# main.net
KiCad netlist of a schematic drawn in Altium Designer
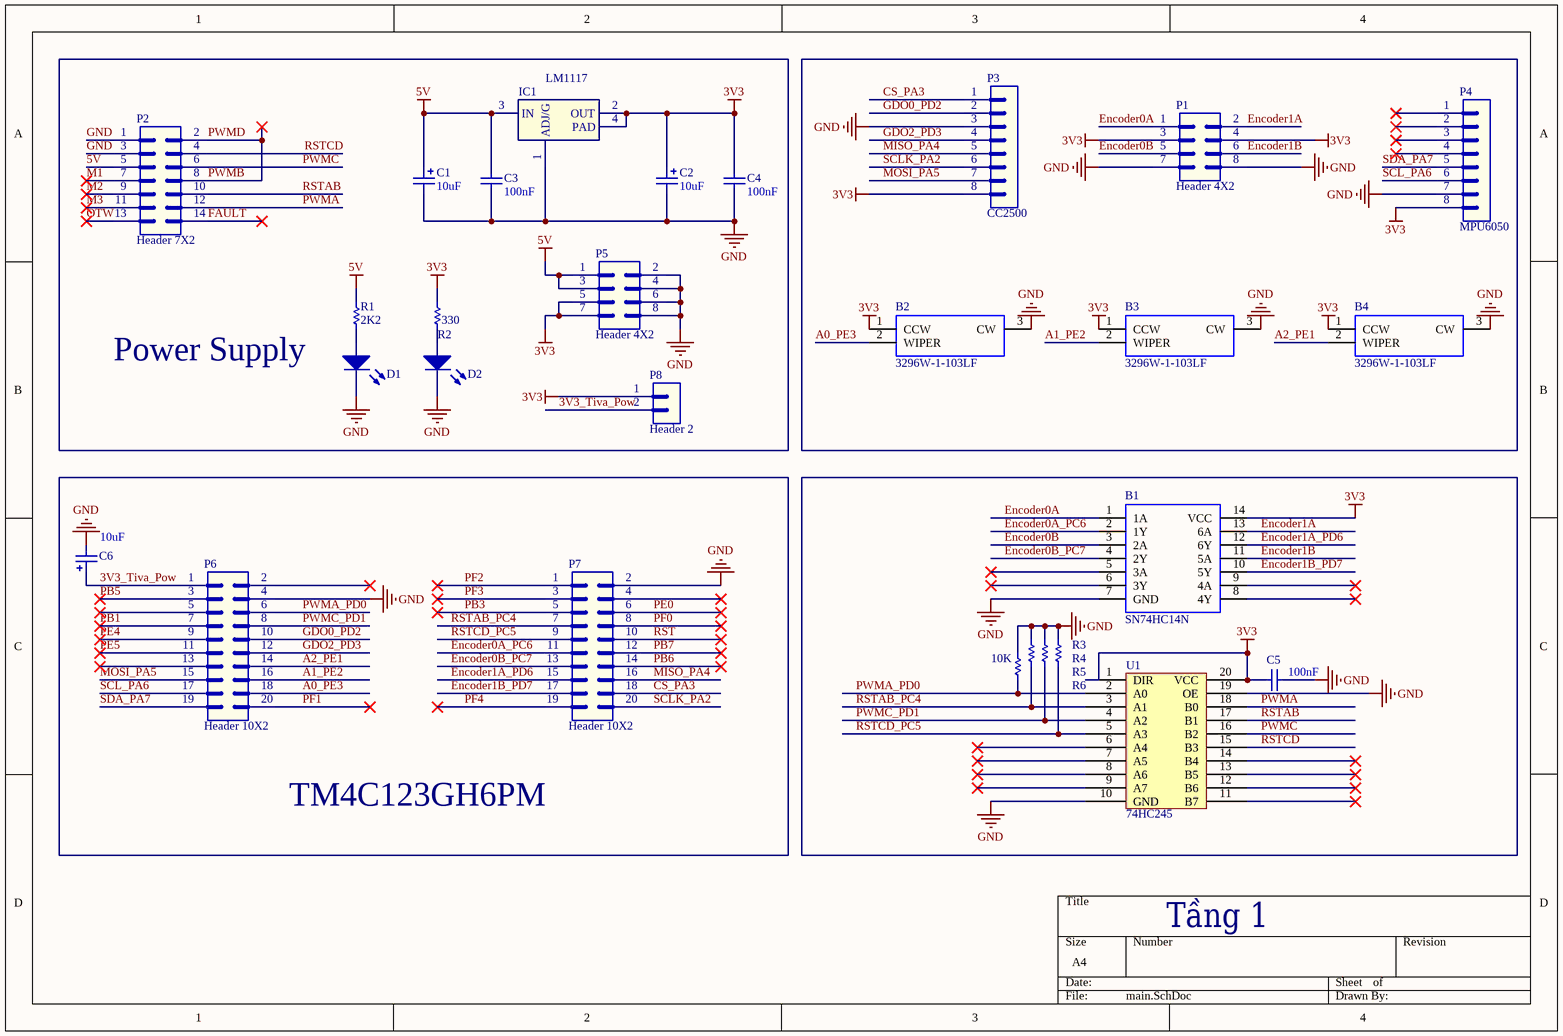
[diagram p0: main.SchDoc]

(export (version "E")
  (design (tool "Eeschema 10.0.6"))
  (components
    (comp (ref "B1")
      (value "SN74HC14N")
      (footprint "DIP254P762X508-14")
      (description "Hex invertor,SN74HC14N DIP14 2-6V 25pcs")
      (fields (field (name "RS PART NUMBER") "0442943"))
      (libsource (lib "SN74HC14N") (part "SN74HC14N"))
    )
    (comp (ref "B2")
      (value "3296W-1-103LF")
      (footprint "SHDR3W54P0X254_1X3_953X483X1155P")
      (fields (field (name "RS PART NUMBER") "5219647P"))
      (libsource (lib "3296W-1-103LF") (part "3296W-1-103LF"))
    )
    (comp (ref "B3")
      (value "3296W-1-103LF")
      (footprint "SHDR3W54P0X254_1X3_953X483X1155P")
      (fields (field (name "RS PART NUMBER") "5219647P"))
      (libsource (lib "3296W-1-103LF") (part "3296W-1-103LF"))
    )
    (comp (ref "B4")
      (value "3296W-1-103LF")
      (footprint "SHDR3W54P0X254_1X3_953X483X1155P")
      (fields (field (name "RS PART NUMBER") "5219647P"))
      (libsource (lib "3296W-1-103LF") (part "3296W-1-103LF"))
    )
    (comp (ref "C1")
      (value "Capacitors")
      (footprint "CAP TANTALUM SMD-1206")
      (description "Capacitors Tantalum")
      (fields
        (field (name "MANUFACTURER") "Kemet")
        (field (name "MANUFACTURER PART NUMBER") "T491A106K010AT")
        (field (name "CAPACITANCE") "10uF")
      )
      (libsource (lib "PIF_C16_lib") (part "Cap Pol Tantalum"))
    )
    (comp (ref "C2")
      (value "Capacitors")
      (footprint "CAP TANTALUM SMD-1206")
      (description "Capacitors Tantalum")
      (fields
        (field (name "MANUFACTURER") "Kemet")
        (field (name "MANUFACTURER PART NUMBER") "T491A106K010AT")
        (field (name "CAPACITANCE") "10uF")
      )
      (libsource (lib "PIF_C16_lib") (part "Cap Pol Tantalum"))
    )
    (comp (ref "C3")
      (value "100nF")
      (footprint "CAP-SM-0805")
      (description "Capacitor")
      (fields (field (name "Comment") "Cap Non-Pol SMD"))
      (libsource (lib "PIF_C16_lib") (part "Cap Non-Pol SMD"))
    )
    (comp (ref "C4")
      (value "100nF")
      (footprint "CAP-SM-0805")
      (description "Capacitor")
      (fields (field (name "Comment") "Cap Non-Pol SMD"))
      (libsource (lib "PIF_C16_lib") (part "Cap Non-Pol SMD"))
    )
    (comp (ref "C5")
      (value "100nF")
      (footprint "CN1")
      (description "Capacitor")
      (fields (field (name "Comment") "Cap Non-Pol"))
      (libsource (lib "PIF_C16_lib") (part "Cap Non-Pol"))
    )
    (comp (ref "C6")
      (value "Capacitors")
      (footprint "CAP TANTALUM SMD-1206")
      (description "Capacitors Tantalum")
      (fields
        (field (name "MANUFACTURER") "Kemet")
        (field (name "MANUFACTURER PART NUMBER") "T491A106K010AT")
        (field (name "CAPACITANCE") "10uF")
      )
      (libsource (lib "PIF_C16_lib") (part "Cap Pol Tantalum"))
    )
    (comp (ref "D1") (value "LED") (footprint "LED-5mm") (libsource (lib "PIF_C16_lib") (part "LED")))
    (comp (ref "D2") (value "LED") (footprint "LED-5mm") (libsource (lib "PIF_C16_lib") (part "LED")))
    (comp (ref "IC1")
      (value "LM1117")
      (footprint "SOT223-4N")
      (description "Available in 1.8V, 2.5V, 2.85V, 3.3V, 5V, and  Adjustable Versions")
      (libsource (lib "PIF_C16_lib") (part "LM1117"))
    )
    (comp (ref "P1")
      (value "Header 4X2")
      (footprint "JP4x2")
      (description "Header, 4-Pin, Dual row")
      (fields (field (name "PUBLISHER") "Altium Limited"))
      (libsource (lib "PIF_C16_lib") (part "Header 4X2"))
    )
    (comp (ref "P2")
      (value "Header 7X2")
      (footprint "JP7X2")
      (description "Header, 7-Pin, Dual row")
      (fields (field (name "PUBLISHER") "Altium Limited"))
      (libsource (lib "PIF_C16_lib") (part "Header 7X2"))
    )
    (comp (ref "P3")
      (value "CC2500")
      (footprint "JP8")
      (description "Header, 8-Pin")
      (fields (field (name "PUBLISHER") "Altium Limited"))
      (libsource (lib "PIF_C16_lib") (part "Header 8"))
    )
    (comp (ref "P4")
      (value "MPU6050")
      (footprint "JP8")
      (description "Header, 8-Pin")
      (fields (field (name "PUBLISHER") "Altium Limited"))
      (libsource (lib "PIF_C16_lib") (part "Header 8"))
    )
    (comp (ref "P5")
      (value "Header 4X2")
      (footprint "JP4x2")
      (description "Header, 4-Pin, Dual row")
      (fields (field (name "PUBLISHER") "Altium Limited"))
      (libsource (lib "PIF_C16_lib") (part "Header 4X2"))
    )
    (comp (ref "P6")
      (value "Header 10X2")
      (footprint "JP10X2")
      (description "Header, 10-Pin, Dual row")
      (fields (field (name "PUBLISHER") "Altium Limited"))
      (libsource (lib "PIF_C16_lib") (part "Header 10X2"))
    )
    (comp (ref "P7")
      (value "Header 10X2")
      (footprint "JP10X2")
      (description "Header, 10-Pin, Dual row")
      (fields (field (name "PUBLISHER") "Altium Limited"))
      (libsource (lib "PIF_C16_lib") (part "Header 10X2"))
    )
    (comp (ref "P8")
      (value "Header 2")
      (footprint "JP2")
      (description "Header, 2-Pin")
      (fields (field (name "PUBLISHER") "Altium Limited"))
      (libsource (lib "PIF_C16_lib") (part "Header 2"))
    )
    (comp (ref "R1")
      (value "2K2")
      (footprint "RES 1/2W")
      (fields (field (name "Comment") "Resistor 1/4W"))
      (libsource (lib "PIF_C16_lib") (part "RES"))
    )
    (comp (ref "R2")
      (value "330")
      (footprint "RES 1/2W")
      (fields (field (name "Comment") "Resistor 1/4W"))
      (libsource (lib "PIF_C16_lib") (part "RES"))
    )
    (comp (ref "R3")
      (value "Resistor 1/4W")
      (footprint "RES 1/2W")
      (libsource (lib "PIF_C16_lib") (part "RES"))
    )
    (comp (ref "R4")
      (value "Resistor 1/4W")
      (footprint "RES 1/2W")
      (libsource (lib "PIF_C16_lib") (part "RES"))
    )
    (comp (ref "R5")
      (value "Resistor 1/4W")
      (footprint "RES 1/2W")
      (libsource (lib "PIF_C16_lib") (part "RES"))
    )
    (comp (ref "R6")
      (value "10K")
      (footprint "RES 1/2W")
      (fields (field (name "Comment") "Resistor 1/4W"))
      (libsource (lib "PIF_C16_lib") (part "RES"))
    )
    (comp (ref "U1")
      (value "74HC245")
      (footprint "DIP20/W0.3")
      (description "Octal bus tranceiver")
      (libsource (lib "syhaunguyen") (part "74HC245"))
    )
  )
  (nets
    (net (code "1") (name "/3V3_Tiva_Pow") (class "Default")
      (node (ref "C6") (pin "1") (pinfunction "1_1") (pintype "passive"))
      (node (ref "P6") (pin "1") (pinfunction "1_1") (pintype "passive"))
      (node (ref "P8") (pin "2") (pinfunction "2_2") (pintype "passive"))
    )
    (net (code "2") (name "/A0_PE3") (class "Default")
      (node (ref "B2") (pin "2") (pinfunction "WIPER_2") (pintype "passive"))
      (node (ref "P6") (pin "18") (pinfunction "18_18") (pintype "passive"))
    )
    (net (code "3") (name "/A1_PE2") (class "Default")
      (node (ref "B3") (pin "2") (pinfunction "WIPER_2") (pintype "passive"))
      (node (ref "P6") (pin "16") (pinfunction "16_16") (pintype "passive"))
    )
    (net (code "4") (name "/A2_PE1") (class "Default")
      (node (ref "B4") (pin "2") (pinfunction "WIPER_2") (pintype "passive"))
      (node (ref "P6") (pin "14") (pinfunction "14_14") (pintype "passive"))
    )
    (net (code "5") (name "/CS_PA3") (class "Default")
      (node (ref "P3") (pin "1") (pinfunction "1_1") (pintype "passive"))
      (node (ref "P7") (pin "18") (pinfunction "18_18") (pintype "passive"))
    )
    (net (code "6") (name "/Encoder0A") (class "Default")
      (node (ref "B1") (pin "1") (pinfunction "1A_1") (pintype "passive"))
      (node (ref "P1") (pin "1") (pinfunction "1_1") (pintype "passive"))
    )
    (net (code "7") (name "/Encoder0A_PC6") (class "Default")
      (node (ref "B1") (pin "2") (pinfunction "1Y_2") (pintype "passive"))
      (node (ref "P7") (pin "11") (pinfunction "11_11") (pintype "passive"))
    )
    (net (code "8") (name "/Encoder0B") (class "Default")
      (node (ref "B1") (pin "3") (pinfunction "2A_3") (pintype "passive"))
      (node (ref "P1") (pin "5") (pinfunction "5_5") (pintype "passive"))
    )
    (net (code "9") (name "/Encoder0B_PC7") (class "Default")
      (node (ref "B1") (pin "4") (pinfunction "2Y_4") (pintype "passive"))
      (node (ref "P7") (pin "13") (pinfunction "13_13") (pintype "passive"))
    )
    (net (code "10") (name "/Encoder1A") (class "Default")
      (node (ref "B1") (pin "13") (pinfunction "6A_13") (pintype "passive"))
      (node (ref "P1") (pin "2") (pinfunction "2_2") (pintype "passive"))
    )
    (net (code "11") (name "/Encoder1A_PD6") (class "Default")
      (node (ref "B1") (pin "12") (pinfunction "6Y_12") (pintype "passive"))
      (node (ref "P7") (pin "15") (pinfunction "15_15") (pintype "passive"))
    )
    (net (code "12") (name "/Encoder1B") (class "Default")
      (node (ref "B1") (pin "11") (pinfunction "5A_11") (pintype "passive"))
      (node (ref "P1") (pin "6") (pinfunction "6_6") (pintype "passive"))
    )
    (net (code "13") (name "/Encoder1B_PD7") (class "Default")
      (node (ref "B1") (pin "10") (pinfunction "5Y_10") (pintype "passive"))
      (node (ref "P7") (pin "17") (pinfunction "17_17") (pintype "passive"))
    )
    (net (code "14") (name "/FAULT") (class "Default")
      (node (ref "P2") (pin "14") (pinfunction "14_14") (pintype "passive+no_connect"))
    )
    (net (code "15") (name "/GDO0_PD2") (class "Default")
      (node (ref "P3") (pin "2") (pinfunction "2_2") (pintype "passive"))
      (node (ref "P6") (pin "10") (pinfunction "10_10") (pintype "passive"))
    )
    (net (code "16") (name "/GDO2_PD3") (class "Default")
      (node (ref "P3") (pin "4") (pinfunction "4_4") (pintype "passive"))
      (node (ref "P6") (pin "12") (pinfunction "12_12") (pintype "passive"))
    )
    (net (code "17") (name "/M1") (class "Default")
      (node (ref "P2") (pin "7") (pinfunction "7_7") (pintype "passive+no_connect"))
    )
    (net (code "18") (name "/M2") (class "Default")
      (node (ref "P2") (pin "9") (pinfunction "9_9") (pintype "passive+no_connect"))
    )
    (net (code "19") (name "/M3") (class "Default")
      (node (ref "P2") (pin "11") (pinfunction "11_11") (pintype "passive+no_connect"))
    )
    (net (code "20") (name "/MISO_PA4") (class "Default")
      (node (ref "P3") (pin "5") (pinfunction "5_5") (pintype "passive"))
      (node (ref "P7") (pin "16") (pinfunction "16_16") (pintype "passive"))
    )
    (net (code "21") (name "/MOSI_PA5") (class "Default")
      (node (ref "P3") (pin "7") (pinfunction "7_7") (pintype "passive"))
      (node (ref "P6") (pin "15") (pinfunction "15_15") (pintype "passive"))
    )
    (net (code "22") (name "/OTW") (class "Default")
      (node (ref "P2") (pin "13") (pinfunction "13_13") (pintype "passive+no_connect"))
    )
    (net (code "23") (name "/PB1") (class "Default")
      (node (ref "P6") (pin "7") (pinfunction "7_7") (pintype "passive+no_connect"))
    )
    (net (code "24") (name "/PB3") (class "Default")
      (node (ref "P7") (pin "5") (pinfunction "5_5") (pintype "passive+no_connect"))
    )
    (net (code "25") (name "/PB5") (class "Default")
      (node (ref "P6") (pin "3") (pinfunction "3_3") (pintype "passive+no_connect"))
    )
    (net (code "26") (name "/PB6") (class "Default")
      (node (ref "P7") (pin "14") (pinfunction "14_14") (pintype "passive+no_connect"))
    )
    (net (code "27") (name "/PB7") (class "Default")
      (node (ref "P7") (pin "12") (pinfunction "12_12") (pintype "passive+no_connect"))
    )
    (net (code "28") (name "/PE0") (class "Default")
      (node (ref "P7") (pin "6") (pinfunction "6_6") (pintype "passive+no_connect"))
    )
    (net (code "29") (name "/PE4") (class "Default")
      (node (ref "P6") (pin "9") (pinfunction "9_9") (pintype "passive+no_connect"))
    )
    (net (code "30") (name "/PE5") (class "Default")
      (node (ref "P6") (pin "11") (pinfunction "11_11") (pintype "passive+no_connect"))
    )
    (net (code "31") (name "/PF0") (class "Default")
      (node (ref "P7") (pin "8") (pinfunction "8_8") (pintype "passive+no_connect"))
    )
    (net (code "32") (name "/PF1") (class "Default")
      (node (ref "P6") (pin "20") (pinfunction "20_20") (pintype "passive+no_connect"))
    )
    (net (code "33") (name "/PF2") (class "Default")
      (node (ref "P7") (pin "1") (pinfunction "1_1") (pintype "passive+no_connect"))
    )
    (net (code "34") (name "/PF3") (class "Default")
      (node (ref "P7") (pin "3") (pinfunction "3_3") (pintype "passive+no_connect"))
    )
    (net (code "35") (name "/PF4") (class "Default")
      (node (ref "P7") (pin "19") (pinfunction "19_19") (pintype "passive+no_connect"))
    )
    (net (code "36") (name "/PWMA") (class "Default")
      (node (ref "P2") (pin "12") (pinfunction "12_12") (pintype "passive"))
      (node (ref "U1") (pin "18") (pinfunction "B0_18") (pintype "passive"))
    )
    (net (code "37") (name "/PWMA_PD0") (class "Default")
      (node (ref "P6") (pin "6") (pinfunction "6_6") (pintype "passive"))
      (node (ref "R6") (pin "1") (pintype "passive"))
      (node (ref "U1") (pin "2") (pinfunction "A0_2") (pintype "passive"))
    )
    (net (code "38") (name "/PWMB") (class "Default")
      (node (ref "P2") (pin "2") (pinfunction "2_2") (pintype "passive"))
      (node (ref "P2") (pin "8") (pinfunction "8_8") (pintype "passive"))
    )
    (net (code "39") (name "/PWMC") (class "Default")
      (node (ref "P2") (pin "6") (pinfunction "6_6") (pintype "passive"))
      (node (ref "U1") (pin "16") (pinfunction "B2_16") (pintype "passive"))
    )
    (net (code "40") (name "/PWMC_PD1") (class "Default")
      (node (ref "P6") (pin "8") (pinfunction "8_8") (pintype "passive"))
      (node (ref "R4") (pin "1") (pintype "passive"))
      (node (ref "U1") (pin "4") (pinfunction "A2_4") (pintype "passive"))
    )
    (net (code "41") (name "/RST") (class "Default")
      (node (ref "P7") (pin "10") (pinfunction "10_10") (pintype "passive+no_connect"))
    )
    (net (code "42") (name "/RSTAB") (class "Default")
      (node (ref "P2") (pin "10") (pinfunction "10_10") (pintype "passive"))
      (node (ref "U1") (pin "17") (pinfunction "B1_17") (pintype "passive"))
    )
    (net (code "43") (name "/RSTAB_PC4") (class "Default")
      (node (ref "P7") (pin "7") (pinfunction "7_7") (pintype "passive"))
      (node (ref "R3") (pin "1") (pintype "passive"))
      (node (ref "U1") (pin "3") (pinfunction "A1_3") (pintype "passive"))
    )
    (net (code "44") (name "/RSTCD") (class "Default")
      (node (ref "P2") (pin "4") (pinfunction "4_4") (pintype "passive"))
      (node (ref "U1") (pin "15") (pinfunction "B3_15") (pintype "passive"))
    )
    (net (code "45") (name "/RSTCD_PC5") (class "Default")
      (node (ref "P7") (pin "9") (pinfunction "9_9") (pintype "passive"))
      (node (ref "R5") (pin "1") (pintype "passive"))
      (node (ref "U1") (pin "5") (pinfunction "A3_5") (pintype "passive"))
    )
    (net (code "46") (name "/SCLK_PA2") (class "Default")
      (node (ref "P3") (pin "6") (pinfunction "6_6") (pintype "passive"))
      (node (ref "P7") (pin "20") (pinfunction "20_20") (pintype "passive"))
    )
    (net (code "47") (name "/SCL_PA6") (class "Default")
      (node (ref "P4") (pin "6") (pinfunction "6_6") (pintype "passive"))
      (node (ref "P6") (pin "17") (pinfunction "17_17") (pintype "passive"))
    )
    (net (code "48") (name "/SDA_PA7") (class "Default")
      (node (ref "P4") (pin "5") (pinfunction "5_5") (pintype "passive"))
      (node (ref "P6") (pin "19") (pinfunction "19_19") (pintype "passive"))
    )
    (net (code "49") (name "3V3") (class "Default")
      (node (ref "B1") (pin "14") (pinfunction "VCC_14") (pintype "passive"))
      (node (ref "B2") (pin "1") (pinfunction "CCW_1") (pintype "passive"))
      (node (ref "B3") (pin "1") (pinfunction "CCW_1") (pintype "passive"))
      (node (ref "B4") (pin "1") (pinfunction "CCW_1") (pintype "passive"))
      (node (ref "C2") (pin "1") (pinfunction "1_1") (pintype "passive"))
      (node (ref "C4") (pin "2") (pinfunction "2_2") (pintype "passive"))
      (node (ref "C5") (pin "1") (pinfunction "1_1") (pintype "passive"))
      (node (ref "IC1") (pin "2") (pinfunction "OUT_2") (pintype "passive"))
      (node (ref "IC1") (pin "4") (pinfunction "PAD_4") (pintype "passive"))
      (node (ref "P1") (pin "3") (pinfunction "3_3") (pintype "passive"))
      (node (ref "P1") (pin "4") (pinfunction "4_4") (pintype "passive"))
      (node (ref "P3") (pin "8") (pinfunction "8_8") (pintype "passive"))
      (node (ref "P4") (pin "8") (pinfunction "8_8") (pintype "passive"))
      (node (ref "P5") (pin "5") (pinfunction "5_5") (pintype "passive"))
      (node (ref "P5") (pin "7") (pinfunction "7_7") (pintype "passive"))
      (node (ref "P8") (pin "1") (pinfunction "1_1") (pintype "passive"))
      (node (ref "R2") (pin "2") (pintype "passive"))
      (node (ref "U1") (pin "1") (pinfunction "DIR_1") (pintype "passive"))
      (node (ref "U1") (pin "20") (pinfunction "VCC_20") (pintype "power_in"))
    )
    (net (code "50") (name "5V") (class "Default")
      (node (ref "C1") (pin "1") (pinfunction "1_1") (pintype "passive"))
      (node (ref "C3") (pin "2") (pinfunction "2_2") (pintype "passive"))
      (node (ref "IC1") (pin "3") (pinfunction "IN_3") (pintype "passive"))
      (node (ref "P2") (pin "5") (pinfunction "5_5") (pintype "passive"))
      (node (ref "P5") (pin "1") (pinfunction "1_1") (pintype "passive"))
      (node (ref "P5") (pin "3") (pinfunction "3_3") (pintype "passive"))
      (node (ref "R1") (pin "2") (pintype "passive"))
    )
    (net (code "51") (name "GND") (class "Default")
      (node (ref "B1") (pin "7") (pinfunction "GND_7") (pintype "passive"))
      (node (ref "B2") (pin "3") (pinfunction "CW_3") (pintype "passive"))
      (node (ref "B3") (pin "3") (pinfunction "CW_3") (pintype "passive"))
      (node (ref "B4") (pin "3") (pinfunction "CW_3") (pintype "passive"))
      (node (ref "C1") (pin "2") (pinfunction "2_2") (pintype "passive"))
      (node (ref "C2") (pin "2") (pinfunction "2_2") (pintype "passive"))
      (node (ref "C3") (pin "1") (pinfunction "1_1") (pintype "passive"))
      (node (ref "C4") (pin "1") (pinfunction "1_1") (pintype "passive"))
      (node (ref "C5") (pin "2") (pinfunction "2_2") (pintype "passive"))
      (node (ref "C6") (pin "2") (pinfunction "2_2") (pintype "passive"))
      (node (ref "D1") (pin "2") (pinfunction "K_2") (pintype "passive"))
      (node (ref "D2") (pin "2") (pinfunction "K_2") (pintype "passive"))
      (node (ref "IC1") (pin "1") (pinfunction "ADJ/G_1") (pintype "passive"))
      (node (ref "P1") (pin "7") (pinfunction "7_7") (pintype "passive"))
      (node (ref "P1") (pin "8") (pinfunction "8_8") (pintype "passive"))
      (node (ref "P2") (pin "1") (pinfunction "1_1") (pintype "passive"))
      (node (ref "P2") (pin "3") (pinfunction "3_3") (pintype "passive"))
      (node (ref "P3") (pin "3") (pinfunction "3_3") (pintype "passive"))
      (node (ref "P4") (pin "7") (pinfunction "7_7") (pintype "passive"))
      (node (ref "P5") (pin "2") (pinfunction "2_2") (pintype "passive"))
      (node (ref "P5") (pin "4") (pinfunction "4_4") (pintype "passive"))
      (node (ref "P5") (pin "6") (pinfunction "6_6") (pintype "passive"))
      (node (ref "P5") (pin "8") (pinfunction "8_8") (pintype "passive"))
      (node (ref "P6") (pin "4") (pinfunction "4_4") (pintype "passive"))
      (node (ref "P7") (pin "2") (pinfunction "2_2") (pintype "passive"))
      (node (ref "R3") (pin "2") (pintype "passive"))
      (node (ref "R4") (pin "2") (pintype "passive"))
      (node (ref "R5") (pin "2") (pintype "passive"))
      (node (ref "R6") (pin "2") (pintype "passive"))
      (node (ref "U1") (pin "10") (pinfunction "GND_10") (pintype "power_in"))
      (node (ref "U1") (pin "19") (pinfunction "OE_19") (pintype "passive"))
    )
    (net (code "52") (name "Net-(D1-A)") (class "Default")
      (node (ref "D1") (pin "1") (pinfunction "A_1") (pintype "passive"))
      (node (ref "R1") (pin "1") (pintype "passive"))
    )
    (net (code "53") (name "Net-(D2-A)") (class "Default")
      (node (ref "D2") (pin "1") (pinfunction "A_1") (pintype "passive"))
      (node (ref "R2") (pin "1") (pintype "passive"))
    )
    (net (code "54") (name "unconnected-(B1-3A-Pad5)") (class "Default")
      (node (ref "B1") (pin "5") (pinfunction "3A_5") (pintype "passive+no_connect"))
    )
    (net (code "55") (name "unconnected-(B1-3Y-Pad6)") (class "Default")
      (node (ref "B1") (pin "6") (pinfunction "3Y_6") (pintype "passive+no_connect"))
    )
    (net (code "56") (name "unconnected-(B1-4A-Pad9)") (class "Default")
      (node (ref "B1") (pin "9") (pinfunction "4A_9") (pintype "passive+no_connect"))
    )
    (net (code "57") (name "unconnected-(B1-4Y-Pad8)") (class "Default")
      (node (ref "B1") (pin "8") (pinfunction "4Y_8") (pintype "passive+no_connect"))
    )
    (net (code "58") (name "unconnected-(P4-Pad1)") (class "Default")
      (node (ref "P4") (pin "1") (pinfunction "1_1") (pintype "passive+no_connect"))
    )
    (net (code "59") (name "unconnected-(P4-Pad2)") (class "Default")
      (node (ref "P4") (pin "2") (pinfunction "2_2") (pintype "passive+no_connect"))
    )
    (net (code "60") (name "unconnected-(P4-Pad3)") (class "Default")
      (node (ref "P4") (pin "3") (pinfunction "3_3") (pintype "passive+no_connect"))
    )
    (net (code "61") (name "unconnected-(P4-Pad4)") (class "Default")
      (node (ref "P4") (pin "4") (pinfunction "4_4") (pintype "passive+no_connect"))
    )
    (net (code "62") (name "unconnected-(P6-Pad2)") (class "Default")
      (node (ref "P6") (pin "2") (pinfunction "2_2") (pintype "passive+no_connect"))
    )
    (net (code "63") (name "unconnected-(P6-Pad5)") (class "Default")
      (node (ref "P6") (pin "5") (pinfunction "5_5") (pintype "passive+no_connect"))
    )
    (net (code "64") (name "unconnected-(P6-Pad13)") (class "Default")
      (node (ref "P6") (pin "13") (pinfunction "13_13") (pintype "passive+no_connect"))
    )
    (net (code "65") (name "unconnected-(P7-Pad4)") (class "Default")
      (node (ref "P7") (pin "4") (pinfunction "4_4") (pintype "passive+no_connect"))
    )
    (net (code "66") (name "unconnected-(U1-A4-Pad6)") (class "Default")
      (node (ref "U1") (pin "6") (pinfunction "A4_6") (pintype "passive+no_connect"))
    )
    (net (code "67") (name "unconnected-(U1-A5-Pad7)") (class "Default")
      (node (ref "U1") (pin "7") (pinfunction "A5_7") (pintype "passive+no_connect"))
    )
    (net (code "68") (name "unconnected-(U1-A6-Pad8)") (class "Default")
      (node (ref "U1") (pin "8") (pinfunction "A6_8") (pintype "passive+no_connect"))
    )
    (net (code "69") (name "unconnected-(U1-A7-Pad9)") (class "Default")
      (node (ref "U1") (pin "9") (pinfunction "A7_9") (pintype "passive+no_connect"))
    )
    (net (code "70") (name "unconnected-(U1-B4-Pad14)") (class "Default")
      (node (ref "U1") (pin "14") (pinfunction "B4_14") (pintype "passive+no_connect"))
    )
    (net (code "71") (name "unconnected-(U1-B5-Pad13)") (class "Default")
      (node (ref "U1") (pin "13") (pinfunction "B5_13") (pintype "passive+no_connect"))
    )
    (net (code "72") (name "unconnected-(U1-B6-Pad12)") (class "Default")
      (node (ref "U1") (pin "12") (pinfunction "B6_12") (pintype "passive+no_connect"))
    )
    (net (code "73") (name "unconnected-(U1-B7-Pad11)") (class "Default")
      (node (ref "U1") (pin "11") (pinfunction "B7_11") (pintype "passive+no_connect"))
    )
  )
)
